# dasblinkenhat-controller-mk-4_1.net
KiCad netlist of a schematic drawn in EAGLE
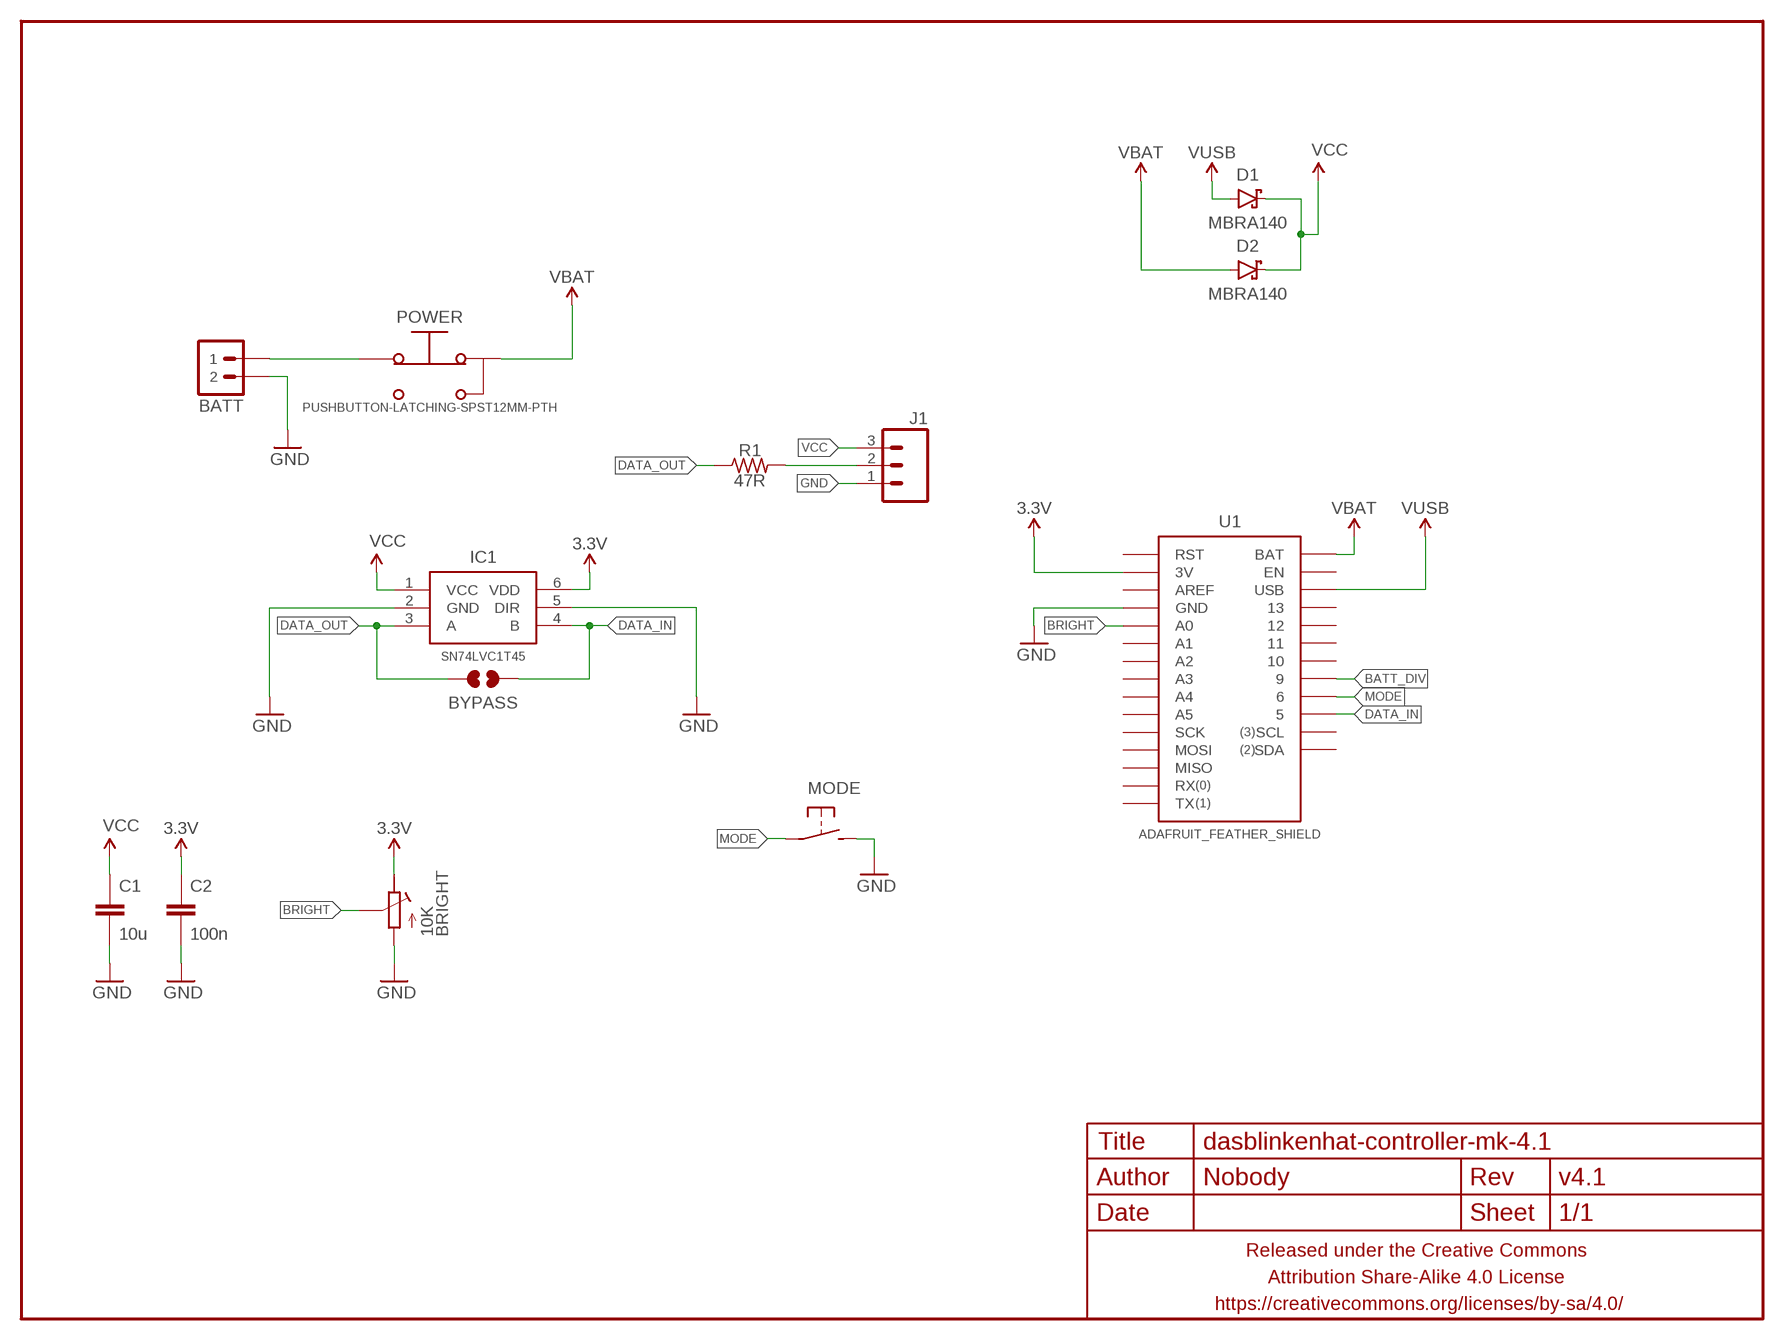
[diagram p0: schematic, sheet 1]

(export (version "E")
  (design (tool "Eeschema 10.0.6"))
  (components
    (comp (ref "BATT")
      (value "M02JST-2MM-SMT")
      (footprint "eagle-import:JST-2-SMD")
      (libsource (lib "eagle-import") (part "M02JST-2MM-SMT"))
    )
    (comp (ref "BRIGHT")
      (value "10K")
      (footprint "eagle-import:EVM3Y")
      (libsource (lib "eagle-import") (part "POTENTIOMETEREVM3Y"))
    )
    (comp (ref "BYPASS")
      (value "JUMPER-PAD-2-NOYES_SILK")
      (footprint "eagle-import:PAD-JUMPER-2-NO_YES_SILK")
      (libsource (lib "eagle-import") (part "JUMPER-PAD-2-NOYES_SILK"))
    )
    (comp (ref "C1")
      (value "10u")
      (footprint "eagle-import:C0805")
      (libsource (lib "eagle-import") (part "CAPACITOR-CERAMICC0805"))
    )
    (comp (ref "C2")
      (value "100n")
      (footprint "eagle-import:C0603")
      (libsource (lib "eagle-import") (part "CAPACITOR-CERAMICC0603"))
    )
    (comp (ref "D1")
      (value "MBRA140")
      (footprint "eagle-import:SMA-DIODE")
      (libsource (lib "eagle-import") (part "DIODE-SCHOTTKYMBRA140"))
    )
    (comp (ref "D2")
      (value "MBRA140")
      (footprint "eagle-import:SMA-DIODE")
      (libsource (lib "eagle-import") (part "DIODE-SCHOTTKYMBRA140"))
    )
    (comp (ref "FRAME1")
      (value "FRAME-LETTERNO_PACKAGE")
      (footprint "eagle-import:DUMMY")
      (fields (field (name "VERSION") "v4.1") (field (name "DESIGNER") "Nobody"))
      (libsource (lib "eagle-import") (part "FRAME-LETTERNO_PACKAGE"))
    )
    (comp (ref "IC1")
      (value "SN74LVC1T45")
      (footprint "eagle-import:SOT23-6")
      (libsource (lib "eagle-import") (part "SN74LVC1T45SOT23-6"))
    )
    (comp (ref "J1")
      (value "M03JST-XH-RA-PTH")
      (footprint "eagle-import:JST-3-XH-RA-PTH")
      (libsource (lib "eagle-import") (part "M03JST-XH-RA-PTH"))
    )
    (comp (ref "MODE")
      (value "DTS-6MM")
      (footprint "eagle-import:TACTILE-PTH-12MM")
      (libsource (lib "eagle-import") (part "SPST-NO-TACT12MM-PTH"))
    )
    (comp (ref "POWER")
      (value "PUSHBUTTON-LATCHING-SPST12MM-PTH")
      (footprint "eagle-import:PUSHBUTTON-CW-SPST-12MM")
      (libsource (lib "eagle-import") (part "PUSHBUTTON-LATCHING-SPST12MM-PTH"))
    )
    (comp (ref "R1")
      (value "47R")
      (footprint "eagle-import:R0603")
      (libsource (lib "eagle-import") (part "RESISTORR0603"))
    )
    (comp (ref "U1")
      (value "ADAFRUIT_FEATHER_SHIELD")
      (footprint "eagle-import:ADAFRUIT_FEATHER")
      (libsource (lib "eagle-import") (part "ADAFRUIT_FEATHER_SHIELD"))
    )
  )
  (nets
    (net (code "1") (name "3.3V") (class "Default")
      (node (ref "BRIGHT") (pin "E") (pinfunction "E_E") (pintype "passive"))
      (node (ref "C2") (pin "1") (pinfunction "1_1") (pintype "passive"))
      (node (ref "IC1") (pin "6") (pinfunction "VDD_6") (pintype "bidirectional"))
      (node (ref "U1") (pin "3V") (pinfunction "3V_3V") (pintype "bidirectional"))
    )
    (net (code "2") (name "BATT_DIV") (class "Default")
      (node (ref "U1") (pin "9") (pinfunction "9_9") (pintype "bidirectional"))
    )
    (net (code "3") (name "BRIGHT") (class "Default")
      (node (ref "BRIGHT") (pin "S") (pinfunction "S_S") (pintype "passive"))
      (node (ref "U1") (pin "A0") (pinfunction "A0_A0") (pintype "bidirectional"))
    )
    (net (code "4") (name "DATA_IN") (class "Default")
      (node (ref "BYPASS") (pin "1") (pinfunction "1_1") (pintype "passive"))
      (node (ref "IC1") (pin "4") (pinfunction "B_4") (pintype "bidirectional"))
      (node (ref "U1") (pin "5") (pinfunction "5_5") (pintype "bidirectional"))
    )
    (net (code "5") (name "DATA_OUT") (class "Default")
      (node (ref "BYPASS") (pin "2") (pinfunction "2_2") (pintype "passive"))
      (node (ref "IC1") (pin "3") (pinfunction "A_3") (pintype "bidirectional"))
      (node (ref "R1") (pin "1") (pinfunction "1_1") (pintype "passive"))
    )
    (net (code "6") (name "GND") (class "Default")
      (node (ref "BATT") (pin "1") (pinfunction "2_1") (pintype "passive"))
      (node (ref "BRIGHT") (pin "A") (pinfunction "A_A") (pintype "passive"))
      (node (ref "C1") (pin "2") (pinfunction "2_2") (pintype "passive"))
      (node (ref "C2") (pin "2") (pinfunction "2_2") (pintype "passive"))
      (node (ref "IC1") (pin "2") (pinfunction "GND_2") (pintype "bidirectional"))
      (node (ref "IC1") (pin "5") (pinfunction "DIR_5") (pintype "bidirectional"))
      (node (ref "J1") (pin "1") (pinfunction "1_1") (pintype "passive"))
      (node (ref "MODE") (pin "3") (pinfunction "2_3") (pintype "passive"))
      (node (ref "MODE") (pin "4") (pinfunction "2_4") (pintype "passive"))
      (node (ref "U1") (pin "GND@0") (pinfunction "GND_GND@0") (pintype "bidirectional"))
      (node (ref "U1") (pin "GND@1") (pinfunction "GND_GND@1") (pintype "bidirectional"))
    )
    (net (code "7") (name "MODE") (class "Default")
      (node (ref "MODE") (pin "1") (pinfunction "1_1") (pintype "passive"))
      (node (ref "MODE") (pin "2") (pinfunction "1_2") (pintype "passive"))
      (node (ref "U1") (pin "6") (pinfunction "6_6") (pintype "bidirectional"))
    )
    (net (code "8") (name "Net-(BATT-1)") (class "Default")
      (node (ref "BATT") (pin "2") (pinfunction "1_2") (pintype "passive"))
      (node (ref "POWER") (pin "2") (pinfunction "NC_2") (pintype "bidirectional"))
    )
    (net (code "9") (name "Net-(J1-Pad2)") (class "Default")
      (node (ref "J1") (pin "2") (pinfunction "2_2") (pintype "passive"))
      (node (ref "R1") (pin "2") (pinfunction "2_2") (pintype "passive"))
    )
    (net (code "10") (name "VBAT") (class "Default")
      (node (ref "D2") (pin "A") (pinfunction "A_A") (pintype "passive"))
      (node (ref "POWER") (pin "1") (pinfunction "COM_1") (pintype "bidirectional"))
      (node (ref "U1") (pin "BAT") (pinfunction "BAT_BAT") (pintype "bidirectional"))
    )
    (net (code "11") (name "VCC") (class "Default")
      (node (ref "C1") (pin "1") (pinfunction "1_1") (pintype "passive"))
      (node (ref "D1") (pin "C") (pinfunction "C_C") (pintype "passive"))
      (node (ref "D2") (pin "C") (pinfunction "C_C") (pintype "passive"))
      (node (ref "IC1") (pin "1") (pinfunction "VCC_1") (pintype "bidirectional"))
      (node (ref "J1") (pin "3") (pinfunction "3_3") (pintype "passive"))
    )
    (net (code "12") (name "VUSB") (class "Default")
      (node (ref "D1") (pin "A") (pinfunction "A_A") (pintype "passive"))
      (node (ref "U1") (pin "USB") (pinfunction "USB_USB") (pintype "bidirectional"))
    )
    (net (code "13") (name "unconnected-(U1-Pad10)") (class "Default")
      (node (ref "U1") (pin "10") (pinfunction "10_10") (pintype "bidirectional"))
    )
    (net (code "14") (name "unconnected-(U1-Pad11)") (class "Default")
      (node (ref "U1") (pin "11") (pinfunction "11_11") (pintype "bidirectional"))
    )
    (net (code "15") (name "unconnected-(U1-Pad12)") (class "Default")
      (node (ref "U1") (pin "12") (pinfunction "12_12") (pintype "bidirectional"))
    )
    (net (code "16") (name "unconnected-(U1-Pad13)") (class "Default")
      (node (ref "U1") (pin "13") (pinfunction "13_13") (pintype "bidirectional"))
    )
    (net (code "17") (name "unconnected-(U1-PadA1)") (class "Default")
      (node (ref "U1") (pin "A1") (pinfunction "A1_A1") (pintype "bidirectional"))
    )
    (net (code "18") (name "unconnected-(U1-PadA2)") (class "Default")
      (node (ref "U1") (pin "A2") (pinfunction "A2_A2") (pintype "bidirectional"))
    )
    (net (code "19") (name "unconnected-(U1-PadA3)") (class "Default")
      (node (ref "U1") (pin "A3") (pinfunction "A3_A3") (pintype "bidirectional"))
    )
    (net (code "20") (name "unconnected-(U1-PadA4)") (class "Default")
      (node (ref "U1") (pin "A4") (pinfunction "A4_A4") (pintype "bidirectional"))
    )
    (net (code "21") (name "unconnected-(U1-PadA5)") (class "Default")
      (node (ref "U1") (pin "A5") (pinfunction "A5_A5") (pintype "bidirectional"))
    )
    (net (code "22") (name "unconnected-(U1-PadAREF)") (class "Default")
      (node (ref "U1") (pin "AREF") (pinfunction "AREF_AREF") (pintype "bidirectional"))
    )
    (net (code "23") (name "unconnected-(U1-PadEN)") (class "Default")
      (node (ref "U1") (pin "EN") (pinfunction "EN_EN") (pintype "bidirectional"))
    )
    (net (code "24") (name "unconnected-(U1-PadMISO)") (class "Default")
      (node (ref "U1") (pin "MISO") (pinfunction "MISO_MISO") (pintype "bidirectional"))
    )
    (net (code "25") (name "unconnected-(U1-PadMOSI)") (class "Default")
      (node (ref "U1") (pin "MOSI") (pinfunction "MOSI_MOSI") (pintype "bidirectional"))
    )
    (net (code "26") (name "unconnected-(U1-PadRST)") (class "Default")
      (node (ref "U1") (pin "RST") (pinfunction "RST_RST") (pintype "bidirectional"))
    )
    (net (code "27") (name "unconnected-(U1-PadRX)") (class "Default")
      (node (ref "U1") (pin "RX") (pinfunction "RX_RX") (pintype "bidirectional"))
    )
    (net (code "28") (name "unconnected-(U1-PadSCK)") (class "Default")
      (node (ref "U1") (pin "SCK") (pinfunction "SCK_SCK") (pintype "bidirectional"))
    )
    (net (code "29") (name "unconnected-(U1-PadSCL)") (class "Default")
      (node (ref "U1") (pin "SCL") (pinfunction "SCL_SCL") (pintype "bidirectional"))
    )
    (net (code "30") (name "unconnected-(U1-PadSDA)") (class "Default")
      (node (ref "U1") (pin "SDA") (pinfunction "SDA_SDA") (pintype "bidirectional"))
    )
    (net (code "31") (name "unconnected-(U1-PadTX)") (class "Default")
      (node (ref "U1") (pin "TX") (pinfunction "TX_TX") (pintype "bidirectional"))
    )
  )
)
